# SMPSBreakout.net
KiCad netlist of a schematic drawn in Altium Designer
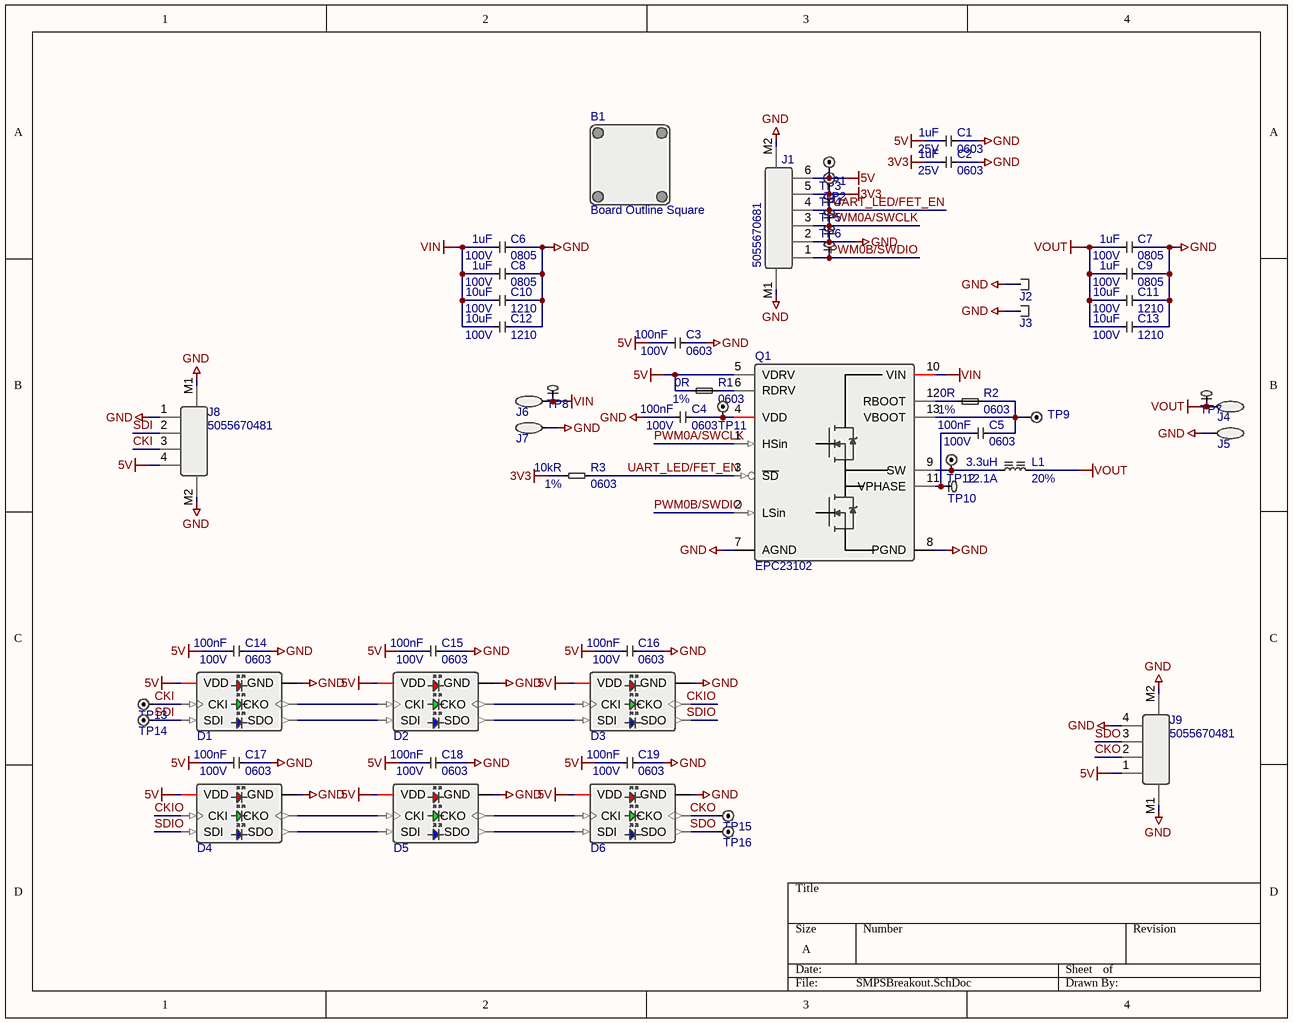
[diagram p0: SMPSBreakout.SchDoc]

(export (version "E")
  (design (tool "Eeschema 10.0.6"))
  (components
    (comp (ref "B1")
      (value "Board Outline Square")
      (footprint "PCB_OUTLINE_SQUARE")
      (libsource (lib "EE490") (part "Board_Outline_Square"))
    )
    (comp (ref "C1")
      (value "1uF")
      (footprint "CAPACITOR_0603(1608)_GENERIC")
      (description "1uF ±20% 25V Ceramic Capacitor X7R 0603(1608 Metric)")
      (fields
        (field (name "VOLTAGE - RATED") "25V")
        (field (name "PACKAGE/CASE IMPERIAL") "0603")
        (field (name "TOLERANCE") "20%")
        (field (name "Comment") "Capacitor - Ceramic - Generic")
      )
      (libsource (lib "EE490") (part "Capacitor - Ceramic - Generic"))
    )
    (comp (ref "C2")
      (value "1uF")
      (footprint "CAPACITOR_0603(1608)_GENERIC")
      (description "1uF ±20% 25V Ceramic Capacitor X7R 0603(1608 Metric)")
      (fields
        (field (name "VOLTAGE - RATED") "25V")
        (field (name "PACKAGE/CASE IMPERIAL") "0603")
        (field (name "TOLERANCE") "20%")
        (field (name "Comment") "Capacitor - Ceramic - Generic")
      )
      (libsource (lib "EE490") (part "Capacitor - Ceramic - Generic"))
    )
    (comp (ref "C3")
      (value "100nF")
      (footprint "CAPACITOR_0603(1608)_GENERIC")
      (description "100nF ±20% 100V Ceramic Capacitor X7R 0603(1608 Metric)")
      (fields
        (field (name "VOLTAGE - RATED") "100V")
        (field (name "PACKAGE/CASE IMPERIAL") "0603")
        (field (name "TOLERANCE") "20%")
        (field (name "Comment") "Capacitor - Ceramic - Generic")
      )
      (libsource (lib "EE490") (part "Capacitor - Ceramic - Generic"))
    )
    (comp (ref "C4")
      (value "100nF")
      (footprint "CAPACITOR_0603(1608)_GENERIC")
      (description "100nF ±20% 100V Ceramic Capacitor X7R 0603(1608 Metric)")
      (fields
        (field (name "VOLTAGE - RATED") "100V")
        (field (name "PACKAGE/CASE IMPERIAL") "0603")
        (field (name "TOLERANCE") "20%")
        (field (name "Comment") "Capacitor - Ceramic - Generic")
      )
      (libsource (lib "EE490") (part "Capacitor - Ceramic - Generic"))
    )
    (comp (ref "C5")
      (value "100nF")
      (footprint "CAPACITOR_0603(1608)_GENERIC")
      (description "100nF ±20% 100V Ceramic Capacitor X7R 0603(1608 Metric)")
      (fields
        (field (name "VOLTAGE - RATED") "100V")
        (field (name "PACKAGE/CASE IMPERIAL") "0603")
        (field (name "TOLERANCE") "20%")
        (field (name "Comment") "Capacitor - Ceramic - Generic")
      )
      (libsource (lib "EE490") (part "Capacitor - Ceramic - Generic"))
    )
    (comp (ref "C6")
      (value "1uF")
      (footprint "CAPACITOR_0805(2012)_GENERIC")
      (description "1uF ±10% 100V Ceramic Capacitor X7S 0805(2012 Metric)")
      (fields
        (field (name "VOLTAGE - RATED") "100V")
        (field (name "PACKAGE/CASE IMPERIAL") "0805")
        (field (name "TOLERANCE") "10%")
        (field (name "Comment") "Capacitor - Ceramic - Generic")
      )
      (libsource (lib "EE490") (part "Capacitor - Ceramic - Generic"))
    )
    (comp (ref "C7")
      (value "1uF")
      (footprint "CAPACITOR_0805(2012)_GENERIC")
      (description "1uF ±10% 100V Ceramic Capacitor X7S 0805(2012 Metric)")
      (fields
        (field (name "VOLTAGE - RATED") "100V")
        (field (name "PACKAGE/CASE IMPERIAL") "0805")
        (field (name "TOLERANCE") "10%")
        (field (name "Comment") "Capacitor - Ceramic - Generic")
      )
      (libsource (lib "EE490") (part "Capacitor - Ceramic - Generic"))
    )
    (comp (ref "C8")
      (value "1uF")
      (footprint "CAPACITOR_0805(2012)_GENERIC")
      (description "1uF ±10% 100V Ceramic Capacitor X7S 0805(2012 Metric)")
      (fields
        (field (name "VOLTAGE - RATED") "100V")
        (field (name "PACKAGE/CASE IMPERIAL") "0805")
        (field (name "TOLERANCE") "10%")
        (field (name "Comment") "Capacitor - Ceramic - Generic")
      )
      (libsource (lib "EE490") (part "Capacitor - Ceramic - Generic"))
    )
    (comp (ref "C9")
      (value "1uF")
      (footprint "CAPACITOR_0805(2012)_GENERIC")
      (description "1uF ±10% 100V Ceramic Capacitor X7S 0805(2012 Metric)")
      (fields
        (field (name "VOLTAGE - RATED") "100V")
        (field (name "PACKAGE/CASE IMPERIAL") "0805")
        (field (name "TOLERANCE") "10%")
        (field (name "Comment") "Capacitor - Ceramic - Generic")
      )
      (libsource (lib "EE490") (part "Capacitor - Ceramic - Generic"))
    )
    (comp (ref "C10")
      (value "10uF")
      (footprint "CAPACITOR_1210(3225)_GENERIC")
      (description "10uF ±20% 100V Ceramic Capacitor X7S 1210(3225 Metric)")
      (fields
        (field (name "VOLTAGE - RATED") "100V")
        (field (name "PACKAGE/CASE IMPERIAL") "1210")
        (field (name "TOLERANCE") "20%")
        (field (name "Comment") "Capacitor - Ceramic - Generic")
      )
      (libsource (lib "EE490") (part "Capacitor - Ceramic - Generic"))
    )
    (comp (ref "C11")
      (value "10uF")
      (footprint "CAPACITOR_1210(3225)_GENERIC")
      (description "10uF ±20% 100V Ceramic Capacitor X7S 1210(3225 Metric)")
      (fields
        (field (name "VOLTAGE - RATED") "100V")
        (field (name "PACKAGE/CASE IMPERIAL") "1210")
        (field (name "TOLERANCE") "20%")
        (field (name "Comment") "Capacitor - Ceramic - Generic")
      )
      (libsource (lib "EE490") (part "Capacitor - Ceramic - Generic"))
    )
    (comp (ref "C12")
      (value "10uF")
      (footprint "CAPACITOR_1210(3225)_GENERIC")
      (description "10uF ±20% 100V Ceramic Capacitor X7S 1210(3225 Metric)")
      (fields
        (field (name "VOLTAGE - RATED") "100V")
        (field (name "PACKAGE/CASE IMPERIAL") "1210")
        (field (name "TOLERANCE") "20%")
        (field (name "Comment") "Capacitor - Ceramic - Generic")
      )
      (libsource (lib "EE490") (part "Capacitor - Ceramic - Generic"))
    )
    (comp (ref "C13")
      (value "10uF")
      (footprint "CAPACITOR_1210(3225)_GENERIC")
      (description "10uF ±20% 100V Ceramic Capacitor X7S 1210(3225 Metric)")
      (fields
        (field (name "VOLTAGE - RATED") "100V")
        (field (name "PACKAGE/CASE IMPERIAL") "1210")
        (field (name "TOLERANCE") "20%")
        (field (name "Comment") "Capacitor - Ceramic - Generic")
      )
      (libsource (lib "EE490") (part "Capacitor - Ceramic - Generic"))
    )
    (comp (ref "C14")
      (value "100nF")
      (footprint "CAPACITOR_0603(1608)_GENERIC")
      (description "100nF ±20% 100V Ceramic Capacitor X7R 0603(1608 Metric)")
      (fields
        (field (name "VOLTAGE - RATED") "100V")
        (field (name "PACKAGE/CASE IMPERIAL") "0603")
        (field (name "TOLERANCE") "20%")
        (field (name "Comment") "Capacitor - Ceramic - Generic")
      )
      (libsource (lib "EE490") (part "Capacitor - Ceramic - Generic"))
    )
    (comp (ref "C15")
      (value "100nF")
      (footprint "CAPACITOR_0603(1608)_GENERIC")
      (description "100nF ±20% 100V Ceramic Capacitor X7R 0603(1608 Metric)")
      (fields
        (field (name "VOLTAGE - RATED") "100V")
        (field (name "PACKAGE/CASE IMPERIAL") "0603")
        (field (name "TOLERANCE") "20%")
        (field (name "Comment") "Capacitor - Ceramic - Generic")
      )
      (libsource (lib "EE490") (part "Capacitor - Ceramic - Generic"))
    )
    (comp (ref "C16")
      (value "100nF")
      (footprint "CAPACITOR_0603(1608)_GENERIC")
      (description "100nF ±20% 100V Ceramic Capacitor X7R 0603(1608 Metric)")
      (fields
        (field (name "VOLTAGE - RATED") "100V")
        (field (name "PACKAGE/CASE IMPERIAL") "0603")
        (field (name "TOLERANCE") "20%")
        (field (name "Comment") "Capacitor - Ceramic - Generic")
      )
      (libsource (lib "EE490") (part "Capacitor - Ceramic - Generic"))
    )
    (comp (ref "C17")
      (value "100nF")
      (footprint "CAPACITOR_0603(1608)_GENERIC")
      (description "100nF ±20% 100V Ceramic Capacitor X7R 0603(1608 Metric)")
      (fields
        (field (name "VOLTAGE - RATED") "100V")
        (field (name "PACKAGE/CASE IMPERIAL") "0603")
        (field (name "TOLERANCE") "20%")
        (field (name "Comment") "Capacitor - Ceramic - Generic")
      )
      (libsource (lib "EE490") (part "Capacitor - Ceramic - Generic"))
    )
    (comp (ref "C18")
      (value "100nF")
      (footprint "CAPACITOR_0603(1608)_GENERIC")
      (description "100nF ±20% 100V Ceramic Capacitor X7R 0603(1608 Metric)")
      (fields
        (field (name "VOLTAGE - RATED") "100V")
        (field (name "PACKAGE/CASE IMPERIAL") "0603")
        (field (name "TOLERANCE") "20%")
        (field (name "Comment") "Capacitor - Ceramic - Generic")
      )
      (libsource (lib "EE490") (part "Capacitor - Ceramic - Generic"))
    )
    (comp (ref "C19")
      (value "100nF")
      (footprint "CAPACITOR_0603(1608)_GENERIC")
      (description "100nF ±20% 100V Ceramic Capacitor X7R 0603(1608 Metric)")
      (fields
        (field (name "VOLTAGE - RATED") "100V")
        (field (name "PACKAGE/CASE IMPERIAL") "0603")
        (field (name "TOLERANCE") "20%")
        (field (name "Comment") "Capacitor - Ceramic - Generic")
      )
      (libsource (lib "EE490") (part "Capacitor - Ceramic - Generic"))
    )
    (comp (ref "D1")
      (value "APA102C")
      (footprint "5X5MM(6PIN)_JLEAD_GENERIC")
      (libsource (lib "EE490") (part "Diode - LED - Addressable - 5x5mm APA102C"))
    )
    (comp (ref "D2")
      (value "APA102C")
      (footprint "5X5MM(6PIN)_JLEAD_GENERIC")
      (libsource (lib "EE490") (part "Diode - LED - Addressable - 5x5mm APA102C"))
    )
    (comp (ref "D3")
      (value "APA102C")
      (footprint "5X5MM(6PIN)_JLEAD_GENERIC")
      (libsource (lib "EE490") (part "Diode - LED - Addressable - 5x5mm APA102C"))
    )
    (comp (ref "D4")
      (value "APA102C")
      (footprint "5X5MM(6PIN)_JLEAD_GENERIC")
      (libsource (lib "EE490") (part "Diode - LED - Addressable - 5x5mm APA102C"))
    )
    (comp (ref "D5")
      (value "APA102C")
      (footprint "5X5MM(6PIN)_JLEAD_GENERIC")
      (libsource (lib "EE490") (part "Diode - LED - Addressable - 5x5mm APA102C"))
    )
    (comp (ref "D6")
      (value "APA102C")
      (footprint "5X5MM(6PIN)_JLEAD_GENERIC")
      (libsource (lib "EE490") (part "Diode - LED - Addressable - 5x5mm APA102C"))
    )
    (comp (ref "J1")
      (value "Connector - Header - 6P 2M - Generic")
      (footprint "CONNECTOR_HEADER_MOLEX_5055670681")
      (description "Connector Header 6 Pin 1.25mm Pitch Mating 50V 2.4A Rated 8 Walls Shrouded SMT Molex 5055670681")
      (fields (field (name "MANUFACTURER PART NUMBER 1") "5055670681"))
      (libsource (lib "EE490") (part "Connector - Header - 6P 2M - Generic"))
    )
    (comp (ref "J2")
      (value "PP45 Staple")
      (footprint "CONNECTOR_ACCESSORY_PP45-STAPLE_ANDERSON")
      (libsource (lib "EE490") (part "Connector - Accessory - Mechanical Support - Anderson PP45 Staple"))
    )
    (comp (ref "J3")
      (value "PP45 Staple")
      (footprint "CONNECTOR_ACCESSORY_PP45-STAPLE_ANDERSON")
      (libsource (lib "EE490") (part "Connector - Accessory - Mechanical Support - Anderson PP45 Staple"))
    )
    (comp (ref "J4")
      (value "PP45")
      (footprint "CONNECTOR_BTOC_PP45_ANDERSON")
      (libsource (lib "EE490") (part "Connector - Modular - 1P - Anderson PP45"))
    )
    (comp (ref "J5")
      (value "PP45")
      (footprint "CONNECTOR_BTOC_PP45_ANDERSON")
      (libsource (lib "EE490") (part "Connector - Modular - 1P - Anderson PP45"))
    )
    (comp (ref "J6")
      (value "PP45")
      (footprint "CONNECTOR_BTOC_PP45_ANDERSON")
      (libsource (lib "EE490") (part "Connector - Modular - 1P - Anderson PP45"))
    )
    (comp (ref "J7")
      (value "PP45")
      (footprint "CONNECTOR_BTOC_PP45_ANDERSON")
      (libsource (lib "EE490") (part "Connector - Modular - 1P - Anderson PP45"))
    )
    (comp (ref "J8")
      (value "Connector - Header - 4P 2M - Generic")
      (footprint "CONNECTOR_HEADER_MOLEX_5055670481")
      (description "Connector Header 4 Pin 1.25mm Pitch Mating 50V 2.4A Rated 6 Walls Shrouded SMT Molex 5055670481")
      (fields (field (name "MANUFACTURER PART NUMBER 1") "5055670481"))
      (libsource (lib "EE490") (part "Connector - Header - 4P 2M - Generic"))
    )
    (comp (ref "J9")
      (value "Connector - Header - 4P 2M - Generic")
      (footprint "CONNECTOR_HEADER_MOLEX_5055670481")
      (description "Connector Header 4 Pin 1.25mm Pitch Mating 50V 2.4A Rated 6 Walls Shrouded SMT Molex 5055670481")
      (fields (field (name "MANUFACTURER PART NUMBER 1") "5055670481"))
      (libsource (lib "EE490") (part "Connector - Header - 4P 2M - Generic"))
    )
    (comp (ref "L1")
      (value "3.3uH")
      (footprint "XGL6060_COILCRAFT")
      (description "Fixed Inductor 3.3uH 20% 5.9mR 12.1A Rated 13.4A Saturation Nonstandard 6.71mmx6.71mm")
      (fields
        (field (name "TOLERANCE") "20%")
        (field (name "CURRENT - RATING") "12.1A")
        (field (name "Comment") "Inductor - Ferrite Core - Generic")
      )
      (libsource (lib "EE490") (part "Inductor - Ferrite Core - Generic"))
    )
    (comp (ref "Q1")
      (value "EPC23102")
      (footprint "QFN-13_EPC_EPC2310X")
      (libsource (lib "EE490") (part "MOSFET - GaN - Integrated Driver EPC 23102"))
    )
    (comp (ref "R1")
      (value "0R")
      (footprint "RESISTOR_0603(1608)_NC_JUMPER")
      (description "0R ±1% 100mW Chip Resistor with Jumper 100ppm/°C 0603(1608 Metric)")
      (fields
        (field (name "TOLERANCE") "1%")
        (field (name "PACKAGE/CASE IMPERIAL") "0603")
        (field (name "POWER") "100mW")
        (field (name "Comment") "Resistor - Fixed - Jumper")
      )
      (libsource (lib "EE490") (part "Resistor - Fixed - Jumper"))
    )
    (comp (ref "R2")
      (value "0R")
      (footprint "RESISTOR_0603(1608)_NC_JUMPER")
      (description "0R ±1% 100mW Chip Resistor with Jumper 100ppm/°C 0603(1608 Metric)")
      (fields
        (field (name "TOLERANCE") "1%")
        (field (name "PACKAGE/CASE IMPERIAL") "0603")
        (field (name "POWER") "100mW")
        (field (name "Comment") "Resistor - Fixed - Jumper")
      )
      (libsource (lib "EE490") (part "Resistor - Fixed - Jumper"))
    )
    (comp (ref "R3")
      (value "10kR")
      (footprint "RESISTOR_0603(1608)_GENERIC")
      (description "10kR ±1% 100mW Chip Resistor 100ppm/°C 0603(1608 Metric)")
      (fields
        (field (name "TOLERANCE") "1%")
        (field (name "PACKAGE/CASE IMPERIAL") "0603")
        (field (name "POWER") "100mW")
        (field (name "Comment") "Resistor - Fixed - Generic")
      )
      (libsource (lib "EE490") (part "Resistor - Fixed - Generic"))
    )
    (comp (ref "TP1")
      (value "Test Point - THT")
      (footprint "TESTPOINT_THT_OCTAGON")
      (libsource (lib "EE490") (part "Test Point - THT"))
    )
    (comp (ref "TP2")
      (value "Test Point - THT")
      (footprint "TESTPOINT_THT_OCTAGON")
      (libsource (lib "EE490") (part "Test Point - THT"))
    )
    (comp (ref "TP3")
      (value "519XTR")
      (footprint "TESTPOINT_LOOP_SMD_KEYSTONE_519X")
      (libsource (lib "EE490") (part "Test Point - SMT - Loop - Keystone 519X"))
    )
    (comp (ref "TP4")
      (value "519XTR")
      (footprint "TESTPOINT_LOOP_SMD_KEYSTONE_519X")
      (libsource (lib "EE490") (part "Test Point - SMT - Loop - Keystone 519X"))
    )
    (comp (ref "TP5")
      (value "519XTR")
      (footprint "TESTPOINT_LOOP_SMD_KEYSTONE_519X")
      (libsource (lib "EE490") (part "Test Point - SMT - Loop - Keystone 519X"))
    )
    (comp (ref "TP6")
      (value "519XTR")
      (footprint "TESTPOINT_LOOP_SMD_KEYSTONE_519X")
      (libsource (lib "EE490") (part "Test Point - SMT - Loop - Keystone 519X"))
    )
    (comp (ref "TP7")
      (value "519XTR")
      (footprint "TESTPOINT_LOOP_SMD_KEYSTONE_519X")
      (libsource (lib "EE490") (part "Test Point - SMT - Loop - Keystone 519X"))
    )
    (comp (ref "TP8")
      (value "519XTR")
      (footprint "TESTPOINT_LOOP_SMD_KEYSTONE_519X")
      (libsource (lib "EE490") (part "Test Point - SMT - Loop - Keystone 519X"))
    )
    (comp (ref "TP9")
      (value "Test Point - THT")
      (footprint "TESTPOINT_THT_OCTAGON")
      (libsource (lib "EE490") (part "Test Point - THT"))
    )
    (comp (ref "TP10")
      (value "519XTR")
      (footprint "TESTPOINT_LOOP_SMD_KEYSTONE_519X")
      (libsource (lib "EE490") (part "Test Point - SMT - Loop - Keystone 519X"))
    )
    (comp (ref "TP11")
      (value "Test Point - THT")
      (footprint "TESTPOINT_THT_OCTAGON")
      (libsource (lib "EE490") (part "Test Point - THT"))
    )
    (comp (ref "TP12")
      (value "Test Point - THT")
      (footprint "TESTPOINT_THT_OCTAGON")
      (libsource (lib "EE490") (part "Test Point - THT"))
    )
    (comp (ref "TP13")
      (value "Test Point - THT")
      (footprint "TESTPOINT_THT_OCTAGON")
      (libsource (lib "EE490") (part "Test Point - THT"))
    )
    (comp (ref "TP14")
      (value "Test Point - THT")
      (footprint "TESTPOINT_THT_OCTAGON")
      (libsource (lib "EE490") (part "Test Point - THT"))
    )
    (comp (ref "TP15")
      (value "Test Point - THT")
      (footprint "TESTPOINT_THT_OCTAGON")
      (libsource (lib "EE490") (part "Test Point - THT"))
    )
    (comp (ref "TP16")
      (value "Test Point - THT")
      (footprint "TESTPOINT_THT_OCTAGON")
      (libsource (lib "EE490") (part "Test Point - THT"))
    )
  )
  (nets
    (net (code "1") (name "/CKI") (class "Default")
      (node (ref "D1") (pin "2") (pinfunction "CKI_2") (pintype "input"))
      (node (ref "J8") (pin "3") (pinfunction "0_3") (pintype "passive"))
      (node (ref "TP13") (pin "1") (pinfunction "1_1") (pintype "passive"))
    )
    (net (code "2") (name "/CKIO") (class "Default")
      (node (ref "D3") (pin "5") (pinfunction "CKO_5") (pintype "output"))
      (node (ref "D4") (pin "2") (pinfunction "CKI_2") (pintype "input"))
    )
    (net (code "3") (name "/CKO") (class "Default")
      (node (ref "D6") (pin "5") (pinfunction "CKO_5") (pintype "output"))
      (node (ref "J9") (pin "2") (pinfunction "0_2") (pintype "passive"))
      (node (ref "TP15") (pin "1") (pinfunction "1_1") (pintype "passive"))
    )
    (net (code "4") (name "/PWM0A{slash}SWCLK") (class "Default")
      (node (ref "J1") (pin "3") (pinfunction "0_3") (pintype "passive"))
      (node (ref "Q1") (pin "1") (pinfunction "HSin_1") (pintype "input"))
      (node (ref "TP4") (pin "1") (pinfunction "1_1") (pintype "passive"))
    )
    (net (code "5") (name "/PWM0B{slash}SWDIO") (class "Default")
      (node (ref "J1") (pin "1") (pinfunction "0_1") (pintype "passive"))
      (node (ref "Q1") (pin "2") (pinfunction "LSin_2") (pintype "input"))
      (node (ref "TP6") (pin "1") (pinfunction "1_1") (pintype "passive"))
    )
    (net (code "6") (name "/SDI") (class "Default")
      (node (ref "D1") (pin "1") (pinfunction "SDI_1") (pintype "input"))
      (node (ref "J8") (pin "2") (pinfunction "0_2") (pintype "passive"))
      (node (ref "TP14") (pin "1") (pinfunction "1_1") (pintype "passive"))
    )
    (net (code "7") (name "/SDIO") (class "Default")
      (node (ref "D3") (pin "6") (pinfunction "SDO_6") (pintype "output"))
      (node (ref "D4") (pin "1") (pinfunction "SDI_1") (pintype "input"))
    )
    (net (code "8") (name "/SDO") (class "Default")
      (node (ref "D6") (pin "6") (pinfunction "SDO_6") (pintype "output"))
      (node (ref "J9") (pin "3") (pinfunction "0_3") (pintype "passive"))
      (node (ref "TP16") (pin "1") (pinfunction "1_1") (pintype "passive"))
    )
    (net (code "9") (name "/UART_LED{slash}FET_EN") (class "Default")
      (node (ref "J1") (pin "4") (pinfunction "0_4") (pintype "passive"))
      (node (ref "Q1") (pin "3") (pinfunction "~{SD}_3") (pintype "input"))
      (node (ref "R3") (pin "2") (pinfunction "2_2") (pintype "passive"))
      (node (ref "TP3") (pin "1") (pinfunction "1_1") (pintype "passive"))
    )
    (net (code "10") (name "3V3") (class "Default")
      (node (ref "C2") (pin "1") (pinfunction "1_1") (pintype "passive"))
      (node (ref "J1") (pin "5") (pinfunction "0_5") (pintype "passive"))
      (node (ref "R3") (pin "1") (pinfunction "1_1") (pintype "passive"))
      (node (ref "TP2") (pin "1") (pinfunction "1_1") (pintype "passive"))
    )
    (net (code "11") (name "5V") (class "Default")
      (node (ref "C1") (pin "1") (pinfunction "1_1") (pintype "passive"))
      (node (ref "C14") (pin "1") (pinfunction "1_1") (pintype "passive"))
      (node (ref "C15") (pin "1") (pinfunction "1_1") (pintype "passive"))
      (node (ref "C16") (pin "1") (pinfunction "1_1") (pintype "passive"))
      (node (ref "C17") (pin "1") (pinfunction "1_1") (pintype "passive"))
      (node (ref "C18") (pin "1") (pinfunction "1_1") (pintype "passive"))
      (node (ref "C19") (pin "1") (pinfunction "1_1") (pintype "passive"))
      (node (ref "C3") (pin "1") (pinfunction "1_1") (pintype "passive"))
      (node (ref "D1") (pin "4") (pinfunction "VDD_4") (pintype "power_in"))
      (node (ref "D2") (pin "4") (pinfunction "VDD_4") (pintype "power_in"))
      (node (ref "D3") (pin "4") (pinfunction "VDD_4") (pintype "power_in"))
      (node (ref "D4") (pin "4") (pinfunction "VDD_4") (pintype "power_in"))
      (node (ref "D5") (pin "4") (pinfunction "VDD_4") (pintype "power_in"))
      (node (ref "D6") (pin "4") (pinfunction "VDD_4") (pintype "power_in"))
      (node (ref "J1") (pin "6") (pinfunction "0_6") (pintype "passive"))
      (node (ref "J8") (pin "4") (pinfunction "0_4") (pintype "passive"))
      (node (ref "J9") (pin "1") (pinfunction "0_1") (pintype "passive"))
      (node (ref "Q1") (pin "5") (pinfunction "VDRV_5") (pintype "power_in"))
      (node (ref "R1") (pin "1") (pinfunction "1_1") (pintype "passive"))
      (node (ref "TP1") (pin "1") (pinfunction "1_1") (pintype "passive"))
    )
    (net (code "12") (name "GND") (class "Default")
      (node (ref "C1") (pin "2") (pinfunction "2_2") (pintype "passive"))
      (node (ref "C10") (pin "2") (pinfunction "2_2") (pintype "passive"))
      (node (ref "C11") (pin "2") (pinfunction "2_2") (pintype "passive"))
      (node (ref "C12") (pin "2") (pinfunction "2_2") (pintype "passive"))
      (node (ref "C13") (pin "2") (pinfunction "2_2") (pintype "passive"))
      (node (ref "C14") (pin "2") (pinfunction "2_2") (pintype "passive"))
      (node (ref "C15") (pin "2") (pinfunction "2_2") (pintype "passive"))
      (node (ref "C16") (pin "2") (pinfunction "2_2") (pintype "passive"))
      (node (ref "C17") (pin "2") (pinfunction "2_2") (pintype "passive"))
      (node (ref "C18") (pin "2") (pinfunction "2_2") (pintype "passive"))
      (node (ref "C19") (pin "2") (pinfunction "2_2") (pintype "passive"))
      (node (ref "C2") (pin "2") (pinfunction "2_2") (pintype "passive"))
      (node (ref "C3") (pin "2") (pinfunction "2_2") (pintype "passive"))
      (node (ref "C4") (pin "1") (pinfunction "1_1") (pintype "passive"))
      (node (ref "C6") (pin "2") (pinfunction "2_2") (pintype "passive"))
      (node (ref "C7") (pin "2") (pinfunction "2_2") (pintype "passive"))
      (node (ref "C8") (pin "2") (pinfunction "2_2") (pintype "passive"))
      (node (ref "C9") (pin "2") (pinfunction "2_2") (pintype "passive"))
      (node (ref "D1") (pin "3") (pinfunction "GND_3") (pintype "power_in"))
      (node (ref "D2") (pin "3") (pinfunction "GND_3") (pintype "power_in"))
      (node (ref "D3") (pin "3") (pinfunction "GND_3") (pintype "power_in"))
      (node (ref "D4") (pin "3") (pinfunction "GND_3") (pintype "power_in"))
      (node (ref "D5") (pin "3") (pinfunction "GND_3") (pintype "power_in"))
      (node (ref "D6") (pin "3") (pinfunction "GND_3") (pintype "power_in"))
      (node (ref "J1") (pin "2") (pinfunction "0_2") (pintype "passive"))
      (node (ref "J1") (pin "M1") (pinfunction "1_M1") (pintype "passive"))
      (node (ref "J1") (pin "M2") (pinfunction "1_M2") (pintype "passive"))
      (node (ref "J2") (pin "1") (pinfunction "1_1") (pintype "passive"))
      (node (ref "J3") (pin "1") (pinfunction "1_1") (pintype "passive"))
      (node (ref "J5") (pin "1") (pinfunction "1_1") (pintype "passive"))
      (node (ref "J7") (pin "1") (pinfunction "1_1") (pintype "passive"))
      (node (ref "J8") (pin "1") (pinfunction "0_1") (pintype "passive"))
      (node (ref "J8") (pin "M1") (pinfunction "1_M1") (pintype "passive"))
      (node (ref "J8") (pin "M2") (pinfunction "1_M2") (pintype "passive"))
      (node (ref "J9") (pin "4") (pinfunction "0_4") (pintype "passive"))
      (node (ref "J9") (pin "M1") (pinfunction "1_M1") (pintype "passive"))
      (node (ref "J9") (pin "M2") (pinfunction "1_M2") (pintype "passive"))
      (node (ref "Q1") (pin "7") (pinfunction "AGND_7") (pintype "power_in"))
      (node (ref "Q1") (pin "8") (pinfunction "PGND_8") (pintype "power_in"))
      (node (ref "TP5") (pin "1") (pinfunction "1_1") (pintype "passive"))
    )
    (net (code "13") (name "Net-(D1-CKO)") (class "Default")
      (node (ref "D1") (pin "5") (pinfunction "CKO_5") (pintype "output"))
      (node (ref "D2") (pin "2") (pinfunction "CKI_2") (pintype "input"))
    )
    (net (code "14") (name "Net-(D1-SDO)") (class "Default")
      (node (ref "D1") (pin "6") (pinfunction "SDO_6") (pintype "output"))
      (node (ref "D2") (pin "1") (pinfunction "SDI_1") (pintype "input"))
    )
    (net (code "15") (name "Net-(D2-CKO)") (class "Default")
      (node (ref "D2") (pin "5") (pinfunction "CKO_5") (pintype "output"))
      (node (ref "D3") (pin "2") (pinfunction "CKI_2") (pintype "input"))
    )
    (net (code "16") (name "Net-(D2-SDO)") (class "Default")
      (node (ref "D2") (pin "6") (pinfunction "SDO_6") (pintype "output"))
      (node (ref "D3") (pin "1") (pinfunction "SDI_1") (pintype "input"))
    )
    (net (code "17") (name "Net-(D4-CKO)") (class "Default")
      (node (ref "D4") (pin "5") (pinfunction "CKO_5") (pintype "output"))
      (node (ref "D5") (pin "2") (pinfunction "CKI_2") (pintype "input"))
    )
    (net (code "18") (name "Net-(D4-SDO)") (class "Default")
      (node (ref "D4") (pin "6") (pinfunction "SDO_6") (pintype "output"))
      (node (ref "D5") (pin "1") (pinfunction "SDI_1") (pintype "input"))
    )
    (net (code "19") (name "Net-(D5-CKO)") (class "Default")
      (node (ref "D5") (pin "5") (pinfunction "CKO_5") (pintype "output"))
      (node (ref "D6") (pin "2") (pinfunction "CKI_2") (pintype "input"))
    )
    (net (code "20") (name "Net-(D5-SDO)") (class "Default")
      (node (ref "D5") (pin "6") (pinfunction "SDO_6") (pintype "output"))
      (node (ref "D6") (pin "1") (pinfunction "SDI_1") (pintype "input"))
    )
    (net (code "21") (name "Net-(Q1-RBOOT)") (class "Default")
      (node (ref "Q1") (pin "12") (pinfunction "RBOOT_12") (pintype "power_in"))
      (node (ref "R2") (pin "1") (pinfunction "1_1") (pintype "passive"))
    )
    (net (code "22") (name "Net-(Q1-RDRV)") (class "Default")
      (node (ref "Q1") (pin "6") (pinfunction "RDRV_6") (pintype "power_in"))
      (node (ref "R1") (pin "2") (pinfunction "2_2") (pintype "passive"))
    )
    (net (code "23") (name "Net-(Q1-SW)") (class "Default")
      (node (ref "L1") (pin "1") (pinfunction "1_1") (pintype "passive"))
      (node (ref "Q1") (pin "9") (pinfunction "SW_9") (pintype "power_in"))
      (node (ref "TP12") (pin "1") (pinfunction "1_1") (pintype "passive"))
    )
    (net (code "24") (name "Net-(Q1-VBOOT)") (class "Default")
      (node (ref "C5") (pin "2") (pinfunction "2_2") (pintype "passive"))
      (node (ref "Q1") (pin "13") (pinfunction "VBOOT_13") (pintype "power_in"))
      (node (ref "R2") (pin "2") (pinfunction "2_2") (pintype "passive"))
      (node (ref "TP9") (pin "1") (pinfunction "1_1") (pintype "passive"))
    )
    (net (code "25") (name "Net-(Q1-VDD)") (class "Default")
      (node (ref "C4") (pin "2") (pinfunction "2_2") (pintype "passive"))
      (node (ref "Q1") (pin "4") (pinfunction "VDD_4") (pintype "power_in"))
      (node (ref "TP11") (pin "1") (pinfunction "1_1") (pintype "passive"))
    )
    (net (code "26") (name "Net-(Q1-VPHASE)") (class "Default")
      (node (ref "C5") (pin "1") (pinfunction "1_1") (pintype "passive"))
      (node (ref "Q1") (pin "11") (pinfunction "VPHASE_11") (pintype "power_in"))
      (node (ref "TP10") (pin "1") (pinfunction "1_1") (pintype "passive"))
    )
    (net (code "27") (name "VIN") (class "Default")
      (node (ref "C10") (pin "1") (pinfunction "1_1") (pintype "passive"))
      (node (ref "C12") (pin "1") (pinfunction "1_1") (pintype "passive"))
      (node (ref "C6") (pin "1") (pinfunction "1_1") (pintype "passive"))
      (node (ref "C8") (pin "1") (pinfunction "1_1") (pintype "passive"))
      (node (ref "J6") (pin "1") (pinfunction "1_1") (pintype "passive"))
      (node (ref "Q1") (pin "10") (pinfunction "VIN_10") (pintype "power_in"))
      (node (ref "TP8") (pin "1") (pinfunction "1_1") (pintype "passive"))
    )
    (net (code "28") (name "VOUT") (class "Default")
      (node (ref "C11") (pin "1") (pinfunction "1_1") (pintype "passive"))
      (node (ref "C13") (pin "1") (pinfunction "1_1") (pintype "passive"))
      (node (ref "C7") (pin "1") (pinfunction "1_1") (pintype "passive"))
      (node (ref "C9") (pin "1") (pinfunction "1_1") (pintype "passive"))
      (node (ref "J4") (pin "1") (pinfunction "1_1") (pintype "passive"))
      (node (ref "L1") (pin "2") (pinfunction "2_2") (pintype "passive"))
      (node (ref "TP7") (pin "1") (pinfunction "1_1") (pintype "passive"))
    )
  )
)
